# main.net
KiCad netlist of a schematic drawn in Altium Designer
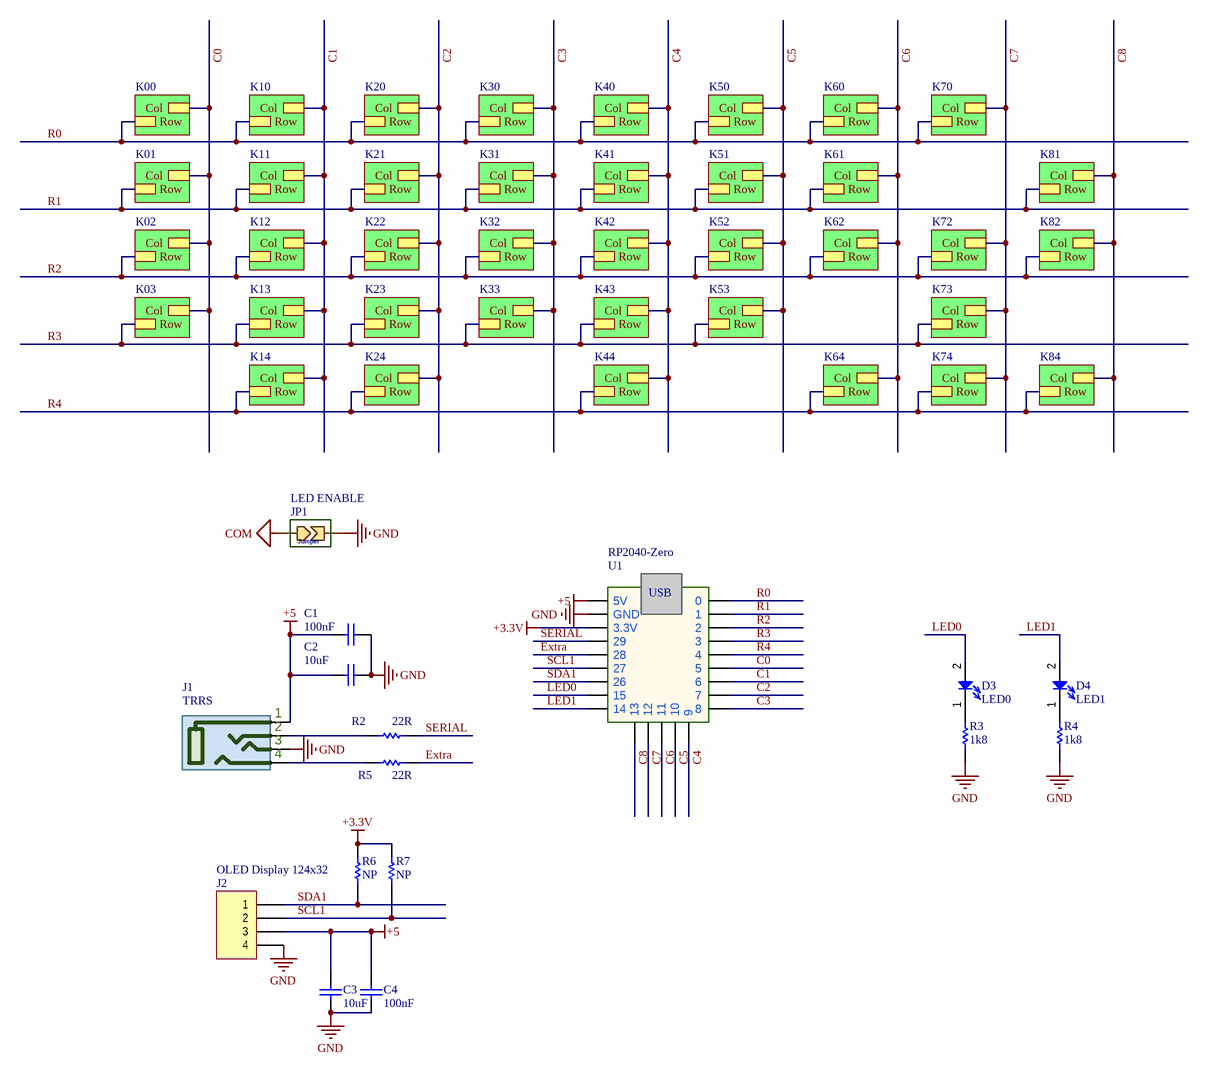
[diagram p0: main.SchDoc]

(export (version "E")
  (design (tool "Eeschema 10.0.6"))
  (components
    (comp (ref "C1")
      (value "100nF")
      (footprint "0402_[1005]")
      (description "Capacitor")
      (libsource (lib "develer_generic") (part "Cap"))
    )
    (comp (ref "C2")
      (value "10uF")
      (footprint "0603_[1608]")
      (description "Capacitor")
      (libsource (lib "develer_generic") (part "Cap"))
    )
    (comp (ref "C3")
      (value "10uF")
      (footprint "0603_[1608]")
      (description "Capacitor")
      (libsource (lib "develer_generic") (part "Cap"))
    )
    (comp (ref "C4")
      (value "100nF")
      (footprint "0402_[1005]")
      (description "Capacitor")
      (libsource (lib "develer_generic") (part "Cap"))
    )
    (comp (ref "D3")
      (value "LED0")
      (footprint "0402_[1005]_K1-A2_LED")
      (description "Diode Led")
      (fields (field (name "PUBLISHER") "Develer srl"))
      (libsource (lib "develer_generic") (part "DiodeLedSmall"))
    )
    (comp (ref "D4")
      (value "LED1")
      (footprint "0402_[1005]_K1-A2_LED")
      (description "Diode Led")
      (fields (field (name "PUBLISHER") "Develer srl"))
      (libsource (lib "develer_generic") (part "DiodeLedSmall"))
    )
    (comp (ref "J1")
      (value "TRRS")
      (footprint "CON_PHONE_TRRS_3.5MM_THD")
      (description "headphone socket TRRS (Hong Cheng HC-PJ-320A)")
      (fields (field (name "PUBLISHER") "Develer srl"))
      (libsource (lib "develer_connectors") (part "CON_PHONE_JACK_TSSR"))
    )
    (comp (ref "J2")
      (value "OLED Display 124x32")
      (footprint "HEADER_1X4_2.54MM_THD")
      (description "Header, 4-Pin")
      (fields (field (name "PUBLISHER") "Altium Limited"))
      (libsource (lib "Miscellaneous Connectors") (part "Header 4"))
    )
    (comp (ref "JP1")
      (value "LED ENABLE")
      (footprint "0603_[1608]_JUMPER")
      (description "Jumper SMD")
      (fields (field (name "PUBLISHER") "Develer srl"))
      (libsource (lib "develer_generic") (part "JumperSMD"))
    )
    (comp (ref "R2")
      (value "22R")
      (footprint "0402_[1005]")
      (description "Resistor")
      (fields (field (name "PUBLISHER") "Develer srl"))
      (libsource (lib "develer_generic") (part "Res"))
    )
    (comp (ref "R3")
      (value "1k8")
      (footprint "0402_[1005]")
      (description "Resistor")
      (fields (field (name "PUBLISHER") "Develer srl"))
      (libsource (lib "develer_generic") (part "Res"))
    )
    (comp (ref "R4")
      (value "1k8")
      (footprint "0402_[1005]")
      (description "Resistor")
      (fields (field (name "PUBLISHER") "Develer srl"))
      (libsource (lib "develer_generic") (part "Res"))
    )
    (comp (ref "R5")
      (value "22R")
      (footprint "0402_[1005]")
      (description "Resistor")
      (fields (field (name "PUBLISHER") "Develer srl"))
      (libsource (lib "develer_generic") (part "Res"))
    )
    (comp (ref "R6")
      (value "NP")
      (footprint "0402_[1005]")
      (description "Resistor")
      (fields (field (name "PUBLISHER") "Develer srl"))
      (libsource (lib "develer_generic") (part "Res"))
    )
    (comp (ref "R7")
      (value "NP")
      (footprint "0402_[1005]")
      (description "Resistor")
      (fields (field (name "PUBLISHER") "Develer srl"))
      (libsource (lib "develer_generic") (part "Res"))
    )
    (comp (ref "U1")
      (value "RP2040-Zero")
      (footprint "RP2040-Zero")
      (description "module, mini based on RP4020 (RP2350-Zero)")
      (fields (field (name "PUBLISHER") "Develer srl"))
      (libsource (lib "develer_components") (part "RP2040-Zero"))
    )
  )
  (nets
    (net (code "1") (name "+3.3V") (class "Default")
      (node (ref "R6") (pin "2") (pinfunction "2_2") (pintype "passive"))
      (node (ref "R7") (pin "2") (pinfunction "2_2") (pintype "passive"))
      (node (ref "U1") (pin "20") (pinfunction "3.3V_20") (pintype "passive"))
    )
    (net (code "2") (name "+5") (class "Default")
      (node (ref "C1") (pin "2") (pinfunction "2_2") (pintype "passive"))
      (node (ref "C2") (pin "2") (pinfunction "2_2") (pintype "passive"))
      (node (ref "C3") (pin "2") (pinfunction "2_2") (pintype "passive"))
      (node (ref "C4") (pin "2") (pinfunction "2_2") (pintype "passive"))
      (node (ref "J1") (pin "1") (pinfunction "1_1") (pintype "passive"))
      (node (ref "J2") (pin "3") (pinfunction "3_3") (pintype "passive"))
      (node (ref "U1") (pin "22") (pinfunction "5V_22") (pintype "passive"))
    )
    (net (code "3") (name "/C0") (class "Default")
      (node (ref "U1") (pin "5") (pinfunction "5_5") (pintype "passive"))
    )
    (net (code "4") (name "/C1") (class "Default")
      (node (ref "U1") (pin "6") (pinfunction "6_6") (pintype "passive"))
    )
    (net (code "5") (name "/C2") (class "Default")
      (node (ref "U1") (pin "7") (pinfunction "7_7") (pintype "passive"))
    )
    (net (code "6") (name "/C3") (class "Default")
      (node (ref "U1") (pin "8") (pinfunction "8_8") (pintype "passive"))
    )
    (net (code "7") (name "/C4") (class "Default")
      (node (ref "U1") (pin "9") (pinfunction "9_9") (pintype "passive"))
    )
    (net (code "8") (name "/C5") (class "Default")
      (node (ref "U1") (pin "10") (pinfunction "10_10") (pintype "passive"))
    )
    (net (code "9") (name "/C6") (class "Default")
      (node (ref "U1") (pin "11") (pinfunction "11_11") (pintype "passive"))
    )
    (net (code "10") (name "/C7") (class "Default")
      (node (ref "U1") (pin "12") (pinfunction "12_12") (pintype "passive"))
    )
    (net (code "11") (name "/C8") (class "Default")
      (node (ref "U1") (pin "13") (pinfunction "13_13") (pintype "passive"))
    )
    (net (code "12") (name "/Extra") (class "Default")
      (node (ref "R5") (pin "1") (pinfunction "1_1") (pintype "passive"))
      (node (ref "U1") (pin "18") (pinfunction "28_18") (pintype "passive"))
    )
    (net (code "13") (name "/LED0") (class "Default")
      (node (ref "D3") (pin "2") (pinfunction "A_2") (pintype "passive"))
      (node (ref "U1") (pin "15") (pinfunction "15_15") (pintype "passive"))
    )
    (net (code "14") (name "/LED1") (class "Default")
      (node (ref "D4") (pin "2") (pinfunction "A_2") (pintype "passive"))
      (node (ref "U1") (pin "14") (pinfunction "14_14") (pintype "passive"))
    )
    (net (code "15") (name "/R0") (class "Default")
      (node (ref "U1") (pin "0") (pinfunction "0_0") (pintype "passive"))
    )
    (net (code "16") (name "/R1") (class "Default")
      (node (ref "U1") (pin "1") (pinfunction "1_1") (pintype "passive"))
    )
    (net (code "17") (name "/R2") (class "Default")
      (node (ref "U1") (pin "2") (pinfunction "2_2") (pintype "passive"))
    )
    (net (code "18") (name "/R3") (class "Default")
      (node (ref "U1") (pin "3") (pinfunction "3_3") (pintype "passive"))
    )
    (net (code "19") (name "/R4") (class "Default")
      (node (ref "U1") (pin "4") (pinfunction "4_4") (pintype "passive"))
    )
    (net (code "20") (name "/SCL1") (class "Default")
      (node (ref "J2") (pin "2") (pinfunction "2_2") (pintype "passive"))
      (node (ref "R7") (pin "1") (pinfunction "1_1") (pintype "passive"))
      (node (ref "U1") (pin "17") (pinfunction "27_17") (pintype "passive"))
    )
    (net (code "21") (name "/SDA1") (class "Default")
      (node (ref "J2") (pin "1") (pinfunction "1_1") (pintype "passive"))
      (node (ref "R6") (pin "1") (pinfunction "1_1") (pintype "passive"))
      (node (ref "U1") (pin "16") (pinfunction "26_16") (pintype "passive"))
    )
    (net (code "22") (name "/SERIAL") (class "Default")
      (node (ref "R2") (pin "1") (pinfunction "1_1") (pintype "passive"))
      (node (ref "U1") (pin "19") (pinfunction "29_19") (pintype "passive"))
    )
    (net (code "23") (name "COM") (class "Default")
      (node (ref "JP1") (pin "1") (pinfunction "1_1") (pintype "passive"))
    )
    (net (code "24") (name "GND") (class "Default")
      (node (ref "C1") (pin "1") (pinfunction "1_1") (pintype "passive"))
      (node (ref "C2") (pin "1") (pinfunction "1_1") (pintype "passive"))
      (node (ref "C3") (pin "1") (pinfunction "1_1") (pintype "passive"))
      (node (ref "C4") (pin "1") (pinfunction "1_1") (pintype "passive"))
      (node (ref "J1") (pin "3") (pinfunction "3_3") (pintype "passive"))
      (node (ref "J2") (pin "4") (pinfunction "4_4") (pintype "passive"))
      (node (ref "JP1") (pin "2") (pinfunction "2_2") (pintype "passive"))
      (node (ref "R3") (pin "1") (pinfunction "1_1") (pintype "passive"))
      (node (ref "R4") (pin "1") (pinfunction "1_1") (pintype "passive"))
      (node (ref "U1") (pin "21") (pinfunction "GND_21") (pintype "passive"))
    )
    (net (code "25") (name "Net-(D3-K)") (class "Default")
      (node (ref "D3") (pin "1") (pinfunction "K_1") (pintype "passive"))
      (node (ref "R3") (pin "2") (pinfunction "2_2") (pintype "passive"))
    )
    (net (code "26") (name "Net-(D4-K)") (class "Default")
      (node (ref "D4") (pin "1") (pinfunction "K_1") (pintype "passive"))
      (node (ref "R4") (pin "2") (pinfunction "2_2") (pintype "passive"))
    )
    (net (code "27") (name "Net-(J1-Pad2)") (class "Default")
      (node (ref "J1") (pin "2") (pinfunction "2_2") (pintype "passive"))
      (node (ref "R2") (pin "2") (pinfunction "2_2") (pintype "passive"))
    )
    (net (code "28") (name "Net-(J1-Pad4)") (class "Default")
      (node (ref "J1") (pin "4") (pinfunction "4_4") (pintype "passive"))
      (node (ref "R5") (pin "2") (pinfunction "2_2") (pintype "passive"))
    )
  )
)
